# MainBoard.net
KiCad netlist of a schematic drawn in Altium Designer
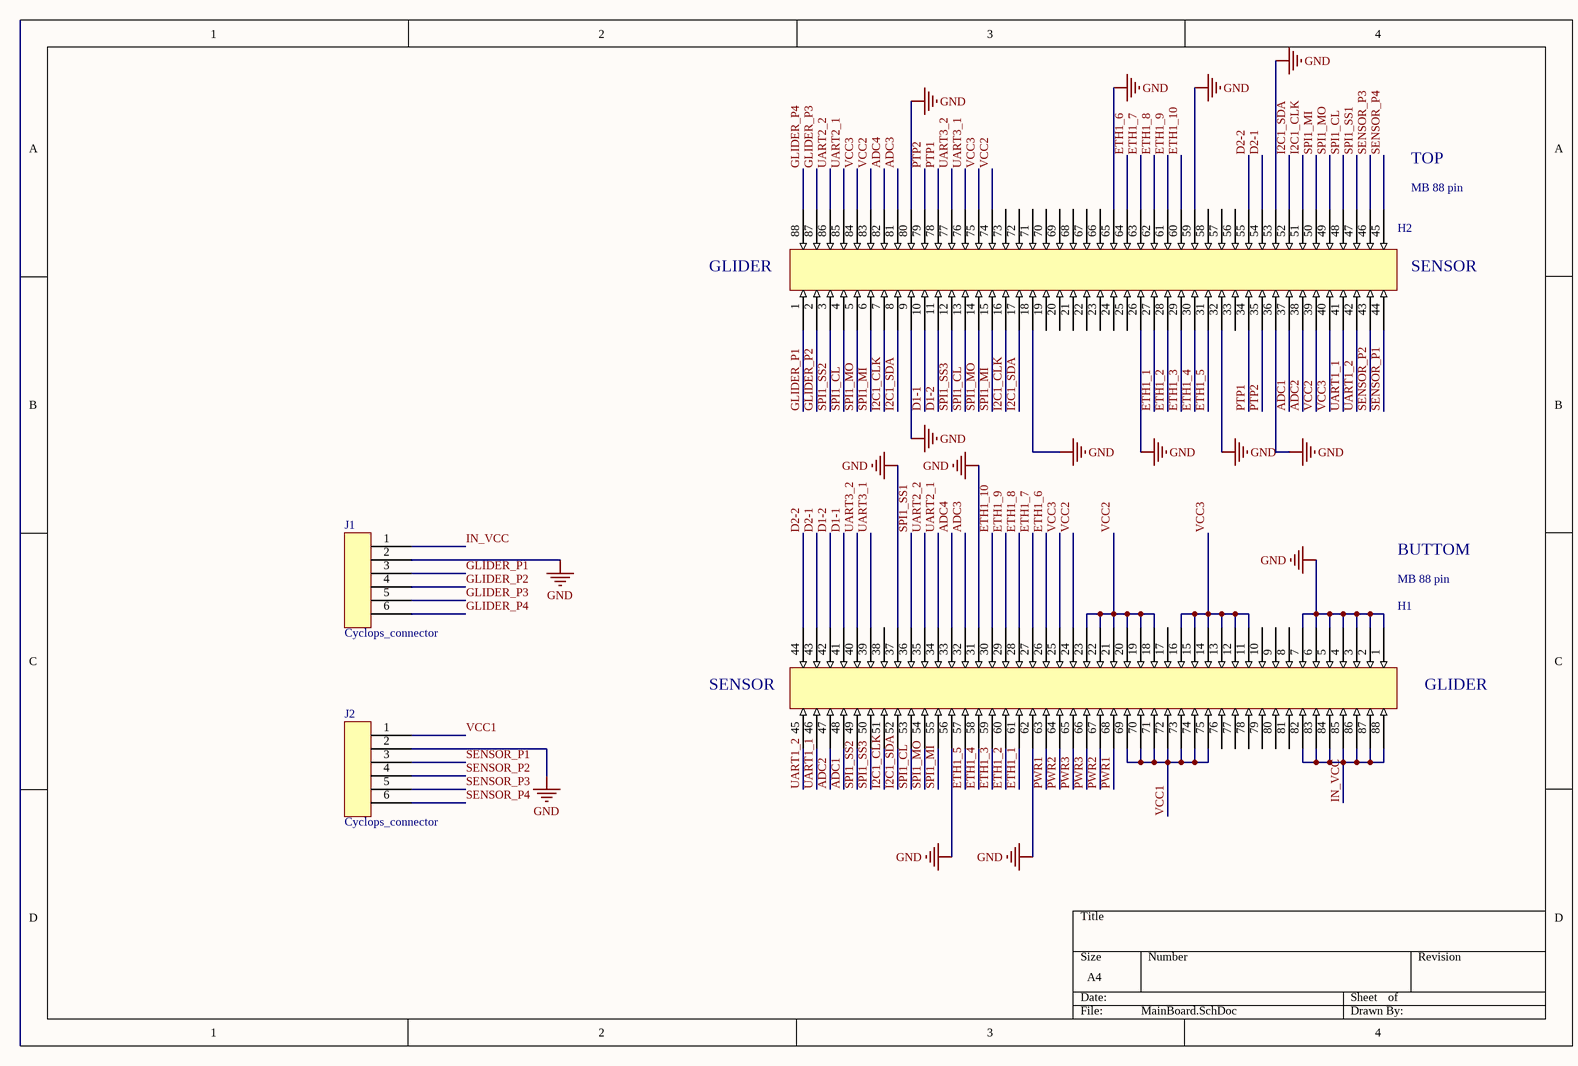
[diagram p0: MainBoard.SchDoc]

(export (version "E")
  (design (tool "Eeschema 10.0.6"))
  (components
    (comp (ref "H1") (value "MB 88 pin") (footprint "MB 88 pins") (libsource (lib "") (part "MB 88 pin_1")))
    (comp (ref "H2") (value "MB 88 pin") (footprint "MB 88 pins") (libsource (lib "USIB") (part "MB 88 pin")))
    (comp (ref "J1")
      (value "Cyclops_connector")
      (footprint "CYCLOPS-1LINE")
      (libsource (lib "Cyclops connector") (part "Cyclops_connector"))
    )
    (comp (ref "J2")
      (value "Cyclops_connector")
      (footprint "CYCLOPS-1LINE")
      (libsource (lib "Cyclops connector") (part "Cyclops_connector"))
    )
  )
  (nets
    (net (code "1") (name "/ADC1") (class "Default")
      (node (ref "H1") (pin "48") (pintype "input"))
      (node (ref "H2") (pin "37") (pintype "input"))
    )
    (net (code "2") (name "/ADC2") (class "Default")
      (node (ref "H1") (pin "47") (pintype "input"))
      (node (ref "H2") (pin "38") (pintype "input"))
    )
    (net (code "3") (name "/ADC3") (class "Default")
      (node (ref "H1") (pin "32") (pintype "input"))
      (node (ref "H2") (pin "81") (pintype "input"))
    )
    (net (code "4") (name "/ADC4") (class "Default")
      (node (ref "H1") (pin "33") (pintype "input"))
      (node (ref "H2") (pin "82") (pintype "input"))
    )
    (net (code "5") (name "/D1-1") (class "Default")
      (node (ref "H1") (pin "41") (pintype "input"))
      (node (ref "H2") (pin "10") (pintype "input"))
    )
    (net (code "6") (name "/D1-2") (class "Default")
      (node (ref "H1") (pin "42") (pintype "input"))
      (node (ref "H2") (pin "11") (pintype "input"))
    )
    (net (code "7") (name "/D2-1") (class "Default")
      (node (ref "H1") (pin "43") (pintype "input"))
      (node (ref "H2") (pin "54") (pintype "input"))
    )
    (net (code "8") (name "/D2-2") (class "Default")
      (node (ref "H1") (pin "44") (pintype "input"))
      (node (ref "H2") (pin "55") (pintype "input"))
    )
    (net (code "9") (name "/ETH1_1") (class "Default")
      (node (ref "H1") (pin "61") (pintype "input"))
      (node (ref "H2") (pin "27") (pintype "input"))
    )
    (net (code "10") (name "/ETH1_2") (class "Default")
      (node (ref "H1") (pin "60") (pintype "input"))
      (node (ref "H2") (pin "28") (pintype "input"))
    )
    (net (code "11") (name "/ETH1_3") (class "Default")
      (node (ref "H1") (pin "59") (pintype "input"))
      (node (ref "H2") (pin "29") (pintype "input"))
    )
    (net (code "12") (name "/ETH1_4") (class "Default")
      (node (ref "H1") (pin "58") (pintype "input"))
      (node (ref "H2") (pin "30") (pintype "input"))
    )
    (net (code "13") (name "/ETH1_5") (class "Default")
      (node (ref "H1") (pin "57") (pintype "input"))
      (node (ref "H2") (pin "31") (pintype "input"))
    )
    (net (code "14") (name "/ETH1_6") (class "Default")
      (node (ref "H1") (pin "26") (pintype "input"))
      (node (ref "H2") (pin "64") (pintype "input"))
    )
    (net (code "15") (name "/ETH1_7") (class "Default")
      (node (ref "H1") (pin "27") (pintype "input"))
      (node (ref "H2") (pin "63") (pintype "input"))
    )
    (net (code "16") (name "/ETH1_8") (class "Default")
      (node (ref "H1") (pin "28") (pintype "input"))
      (node (ref "H2") (pin "62") (pintype "input"))
    )
    (net (code "17") (name "/ETH1_9") (class "Default")
      (node (ref "H1") (pin "29") (pintype "input"))
      (node (ref "H2") (pin "61") (pintype "input"))
    )
    (net (code "18") (name "/ETH1_10") (class "Default")
      (node (ref "H1") (pin "30") (pintype "input"))
      (node (ref "H2") (pin "60") (pintype "input"))
    )
    (net (code "19") (name "/GLIDER_P1") (class "Default")
      (node (ref "H2") (pin "1") (pintype "input"))
      (node (ref "J1") (pin "3") (pintype "passive"))
    )
    (net (code "20") (name "/GLIDER_P2") (class "Default")
      (node (ref "H2") (pin "2") (pintype "input"))
      (node (ref "J1") (pin "4") (pintype "passive"))
    )
    (net (code "21") (name "/GLIDER_P3") (class "Default")
      (node (ref "H2") (pin "87") (pintype "input"))
      (node (ref "J1") (pin "5") (pintype "passive"))
    )
    (net (code "22") (name "/GLIDER_P4") (class "Default")
      (node (ref "H2") (pin "88") (pintype "input"))
      (node (ref "J1") (pin "6") (pintype "passive"))
    )
    (net (code "23") (name "/I2C1_CLK") (class "Default")
      (node (ref "H1") (pin "51") (pintype "input"))
      (node (ref "H2") (pin "16") (pintype "input"))
      (node (ref "H2") (pin "51") (pintype "input"))
      (node (ref "H2") (pin "7") (pintype "input"))
    )
    (net (code "24") (name "/I2C1_SDA") (class "Default")
      (node (ref "H1") (pin "52") (pintype "input"))
      (node (ref "H2") (pin "17") (pintype "input"))
      (node (ref "H2") (pin "52") (pintype "input"))
      (node (ref "H2") (pin "8") (pintype "input"))
    )
    (net (code "25") (name "/IN_VCC") (class "Default")
      (node (ref "H1") (pin "82") (pintype "input"))
      (node (ref "H1") (pin "83") (pintype "input"))
      (node (ref "H1") (pin "84") (pintype "input"))
      (node (ref "H1") (pin "85") (pintype "input"))
      (node (ref "H1") (pin "86") (pintype "input"))
      (node (ref "H1") (pin "87") (pintype "input"))
      (node (ref "H1") (pin "88") (pintype "input"))
      (node (ref "J1") (pin "1") (pintype "passive"))
    )
    (net (code "26") (name "/PTP1") (class "Default")
      (node (ref "H2") (pin "34") (pintype "input"))
      (node (ref "H2") (pin "78") (pintype "input"))
    )
    (net (code "27") (name "/PTP2") (class "Default")
      (node (ref "H2") (pin "35") (pintype "input"))
      (node (ref "H2") (pin "79") (pintype "input"))
    )
    (net (code "28") (name "/PWR1") (class "Default")
      (node (ref "H1") (pin "63") (pintype "input"))
      (node (ref "H1") (pin "68") (pintype "input"))
    )
    (net (code "29") (name "/PWR2") (class "Default")
      (node (ref "H1") (pin "64") (pintype "input"))
      (node (ref "H1") (pin "67") (pintype "input"))
    )
    (net (code "30") (name "/PWR3") (class "Default")
      (node (ref "H1") (pin "65") (pintype "input"))
      (node (ref "H1") (pin "66") (pintype "input"))
    )
    (net (code "31") (name "/SENSOR_P1") (class "Default")
      (node (ref "H2") (pin "44") (pintype "input"))
      (node (ref "J2") (pin "3") (pintype "passive"))
    )
    (net (code "32") (name "/SENSOR_P2") (class "Default")
      (node (ref "H2") (pin "43") (pintype "input"))
      (node (ref "J2") (pin "4") (pintype "passive"))
    )
    (net (code "33") (name "/SENSOR_P3") (class "Default")
      (node (ref "H2") (pin "46") (pintype "input"))
      (node (ref "J2") (pin "5") (pintype "passive"))
    )
    (net (code "34") (name "/SENSOR_P4") (class "Default")
      (node (ref "H2") (pin "45") (pintype "input"))
      (node (ref "J2") (pin "6") (pintype "passive"))
    )
    (net (code "35") (name "/SPI1_CL") (class "Default")
      (node (ref "H1") (pin "53") (pintype "input"))
      (node (ref "H2") (pin "13") (pintype "input"))
      (node (ref "H2") (pin "4") (pintype "input"))
      (node (ref "H2") (pin "48") (pintype "input"))
    )
    (net (code "36") (name "/SPI1_MI") (class "Default")
      (node (ref "H1") (pin "55") (pintype "input"))
      (node (ref "H2") (pin "15") (pintype "input"))
      (node (ref "H2") (pin "50") (pintype "input"))
      (node (ref "H2") (pin "6") (pintype "input"))
    )
    (net (code "37") (name "/SPI1_MO") (class "Default")
      (node (ref "H1") (pin "54") (pintype "input"))
      (node (ref "H2") (pin "14") (pintype "input"))
      (node (ref "H2") (pin "49") (pintype "input"))
      (node (ref "H2") (pin "5") (pintype "input"))
    )
    (net (code "38") (name "/SPI1_SS1") (class "Default")
      (node (ref "H1") (pin "36") (pintype "input"))
      (node (ref "H2") (pin "47") (pintype "input"))
    )
    (net (code "39") (name "/SPI1_SS2") (class "Default")
      (node (ref "H1") (pin "49") (pintype "input"))
      (node (ref "H2") (pin "3") (pintype "input"))
    )
    (net (code "40") (name "/SPI1_SS3") (class "Default")
      (node (ref "H1") (pin "50") (pintype "input"))
      (node (ref "H2") (pin "12") (pintype "input"))
    )
    (net (code "41") (name "/UART1_1") (class "Default")
      (node (ref "H1") (pin "46") (pintype "input"))
      (node (ref "H2") (pin "41") (pintype "input"))
    )
    (net (code "42") (name "/UART1_2") (class "Default")
      (node (ref "H1") (pin "45") (pintype "input"))
      (node (ref "H2") (pin "42") (pintype "input"))
    )
    (net (code "43") (name "/UART2_1") (class "Default")
      (node (ref "H1") (pin "34") (pintype "input"))
      (node (ref "H2") (pin "85") (pintype "input"))
    )
    (net (code "44") (name "/UART2_2") (class "Default")
      (node (ref "H1") (pin "35") (pintype "input"))
      (node (ref "H2") (pin "86") (pintype "input"))
    )
    (net (code "45") (name "/UART3_1") (class "Default")
      (node (ref "H1") (pin "39") (pintype "input"))
      (node (ref "H2") (pin "76") (pintype "input"))
    )
    (net (code "46") (name "/UART3_2") (class "Default")
      (node (ref "H1") (pin "40") (pintype "input"))
      (node (ref "H2") (pin "77") (pintype "input"))
    )
    (net (code "47") (name "/VCC1") (class "Default")
      (node (ref "H1") (pin "69") (pintype "input"))
      (node (ref "H1") (pin "70") (pintype "input"))
      (node (ref "H1") (pin "71") (pintype "input"))
      (node (ref "H1") (pin "72") (pintype "input"))
      (node (ref "H1") (pin "73") (pintype "input"))
      (node (ref "H1") (pin "74") (pintype "input"))
      (node (ref "H1") (pin "75") (pintype "input"))
      (node (ref "J2") (pin "1") (pintype "passive"))
    )
    (net (code "48") (name "/VCC2") (class "Default")
      (node (ref "H1") (pin "18") (pintype "input"))
      (node (ref "H1") (pin "19") (pintype "input"))
      (node (ref "H1") (pin "20") (pintype "input"))
      (node (ref "H1") (pin "21") (pintype "input"))
      (node (ref "H1") (pin "22") (pintype "input"))
      (node (ref "H1") (pin "23") (pintype "input"))
      (node (ref "H1") (pin "24") (pintype "input"))
      (node (ref "H2") (pin "39") (pintype "input"))
      (node (ref "H2") (pin "74") (pintype "input"))
      (node (ref "H2") (pin "83") (pintype "input"))
    )
    (net (code "49") (name "/VCC3") (class "Default")
      (node (ref "H1") (pin "11") (pintype "input"))
      (node (ref "H1") (pin "12") (pintype "input"))
      (node (ref "H1") (pin "13") (pintype "input"))
      (node (ref "H1") (pin "14") (pintype "input"))
      (node (ref "H1") (pin "15") (pintype "input"))
      (node (ref "H1") (pin "16") (pintype "input"))
      (node (ref "H1") (pin "25") (pintype "input"))
      (node (ref "H2") (pin "40") (pintype "input"))
      (node (ref "H2") (pin "75") (pintype "input"))
      (node (ref "H2") (pin "84") (pintype "input"))
    )
    (net (code "50") (name "GND") (class "Default")
      (node (ref "H1") (pin "1") (pintype "input"))
      (node (ref "H1") (pin "2") (pintype "input"))
      (node (ref "H1") (pin "3") (pintype "input"))
      (node (ref "H1") (pin "31") (pintype "input"))
      (node (ref "H1") (pin "37") (pintype "input"))
      (node (ref "H1") (pin "4") (pintype "input"))
      (node (ref "H1") (pin "5") (pintype "input"))
      (node (ref "H1") (pin "56") (pintype "input"))
      (node (ref "H1") (pin "6") (pintype "input"))
      (node (ref "H1") (pin "62") (pintype "input"))
      (node (ref "H1") (pin "7") (pintype "input"))
      (node (ref "H2") (pin "18") (pintype "input"))
      (node (ref "H2") (pin "26") (pintype "input"))
      (node (ref "H2") (pin "32") (pintype "input"))
      (node (ref "H2") (pin "36") (pintype "input"))
      (node (ref "H2") (pin "53") (pintype "input"))
      (node (ref "H2") (pin "59") (pintype "input"))
      (node (ref "H2") (pin "65") (pintype "input"))
      (node (ref "H2") (pin "80") (pintype "input"))
      (node (ref "H2") (pin "9") (pintype "input"))
      (node (ref "J1") (pin "2") (pintype "passive"))
      (node (ref "J2") (pin "2") (pintype "passive"))
    )
    (net (code "51") (name "unconnected-(H1-Pad8)") (class "Default")
      (node (ref "H1") (pin "8") (pintype "input"))
    )
    (net (code "52") (name "unconnected-(H1-Pad9)") (class "Default")
      (node (ref "H1") (pin "9") (pintype "input"))
    )
    (net (code "53") (name "unconnected-(H1-Pad10)") (class "Default")
      (node (ref "H1") (pin "10") (pintype "input"))
    )
    (net (code "54") (name "unconnected-(H1-Pad17)") (class "Default")
      (node (ref "H1") (pin "17") (pintype "input"))
    )
    (net (code "55") (name "unconnected-(H1-Pad38)") (class "Default")
      (node (ref "H1") (pin "38") (pintype "input"))
    )
    (net (code "56") (name "unconnected-(H1-Pad76)") (class "Default")
      (node (ref "H1") (pin "76") (pintype "input"))
    )
    (net (code "57") (name "unconnected-(H1-Pad77)") (class "Default")
      (node (ref "H1") (pin "77") (pintype "input"))
    )
    (net (code "58") (name "unconnected-(H1-Pad78)") (class "Default")
      (node (ref "H1") (pin "78") (pintype "input"))
    )
    (net (code "59") (name "unconnected-(H1-Pad79)") (class "Default")
      (node (ref "H1") (pin "79") (pintype "input"))
    )
    (net (code "60") (name "unconnected-(H1-Pad80)") (class "Default")
      (node (ref "H1") (pin "80") (pintype "input"))
    )
    (net (code "61") (name "unconnected-(H1-Pad81)") (class "Default")
      (node (ref "H1") (pin "81") (pintype "input"))
    )
    (net (code "62") (name "unconnected-(H2-Pad19)") (class "Default")
      (node (ref "H2") (pin "19") (pintype "input"))
    )
    (net (code "63") (name "unconnected-(H2-Pad20)") (class "Default")
      (node (ref "H2") (pin "20") (pintype "input"))
    )
    (net (code "64") (name "unconnected-(H2-Pad21)") (class "Default")
      (node (ref "H2") (pin "21") (pintype "input"))
    )
    (net (code "65") (name "unconnected-(H2-Pad22)") (class "Default")
      (node (ref "H2") (pin "22") (pintype "input"))
    )
    (net (code "66") (name "unconnected-(H2-Pad23)") (class "Default")
      (node (ref "H2") (pin "23") (pintype "input"))
    )
    (net (code "67") (name "unconnected-(H2-Pad24)") (class "Default")
      (node (ref "H2") (pin "24") (pintype "input"))
    )
    (net (code "68") (name "unconnected-(H2-Pad25)") (class "Default")
      (node (ref "H2") (pin "25") (pintype "input"))
    )
    (net (code "69") (name "unconnected-(H2-Pad33)") (class "Default")
      (node (ref "H2") (pin "33") (pintype "input"))
    )
    (net (code "70") (name "unconnected-(H2-Pad56)") (class "Default")
      (node (ref "H2") (pin "56") (pintype "input"))
    )
    (net (code "71") (name "unconnected-(H2-Pad57)") (class "Default")
      (node (ref "H2") (pin "57") (pintype "input"))
    )
    (net (code "72") (name "unconnected-(H2-Pad58)") (class "Default")
      (node (ref "H2") (pin "58") (pintype "input"))
    )
    (net (code "73") (name "unconnected-(H2-Pad66)") (class "Default")
      (node (ref "H2") (pin "66") (pintype "input"))
    )
    (net (code "74") (name "unconnected-(H2-Pad67)") (class "Default")
      (node (ref "H2") (pin "67") (pintype "input"))
    )
    (net (code "75") (name "unconnected-(H2-Pad68)") (class "Default")
      (node (ref "H2") (pin "68") (pintype "input"))
    )
    (net (code "76") (name "unconnected-(H2-Pad69)") (class "Default")
      (node (ref "H2") (pin "69") (pintype "input"))
    )
    (net (code "77") (name "unconnected-(H2-Pad70)") (class "Default")
      (node (ref "H2") (pin "70") (pintype "input"))
    )
    (net (code "78") (name "unconnected-(H2-Pad71)") (class "Default")
      (node (ref "H2") (pin "71") (pintype "input"))
    )
    (net (code "79") (name "unconnected-(H2-Pad72)") (class "Default")
      (node (ref "H2") (pin "72") (pintype "input"))
    )
    (net (code "80") (name "unconnected-(H2-Pad73)") (class "Default")
      (node (ref "H2") (pin "73") (pintype "input"))
    )
  )
)
